# emonTx4-ESP32.net
KiCad netlist of a schematic drawn in EAGLE
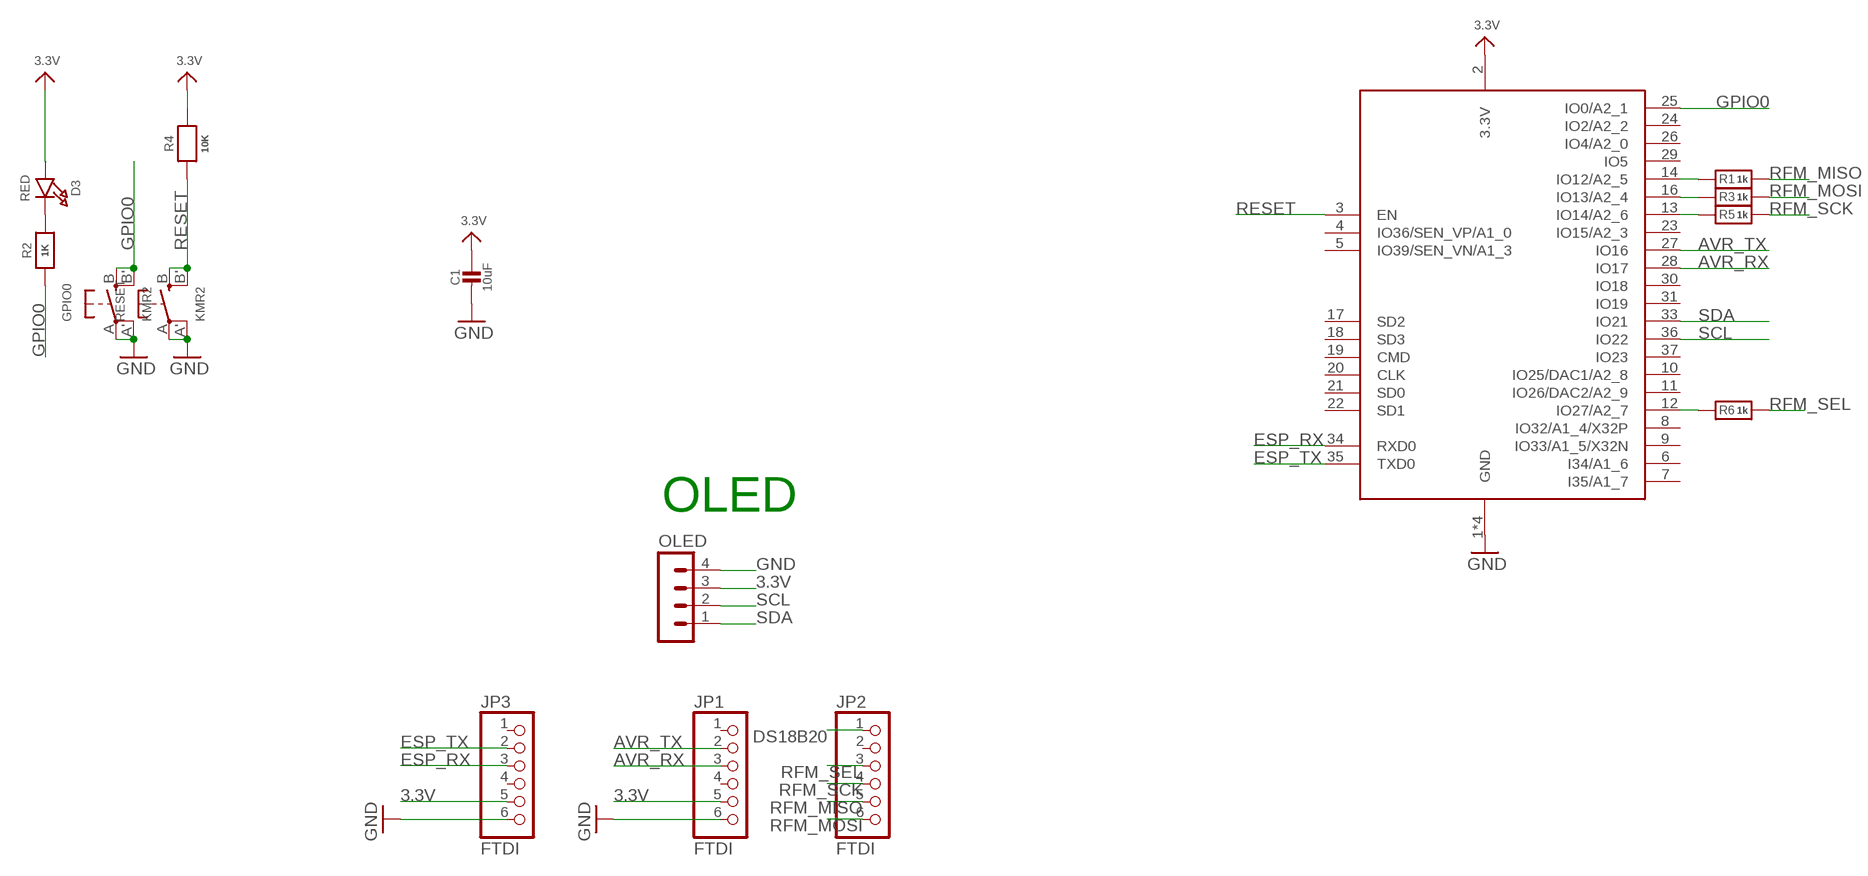
[diagram p0: schematic, sheet 1]

(export (version "E")
  (design (tool "Eeschema 10.0.6"))
  (components
    (comp (ref "C1")
      (value "10uF")
      (footprint "eagle-import:_0603")
      (libsource (lib "eagle-import") (part "CAP_CERAMIC_0603"))
    )
    (comp (ref "D3")
      (value "RED")
      (footprint "eagle-import:CHIPLED_0603")
      (libsource (lib "eagle-import") (part "LED0603"))
    )
    (comp (ref "GPIO0")
      (value "KMR2")
      (footprint "eagle-import:BTN_KMR2_4.6X2.8")
      (libsource (lib "eagle-import") (part "SWITCH_TACT_SMT4.6X2.8"))
    )
    (comp (ref "JP1")
      (value "FTDI")
      (footprint "eagle-import:1X06_ROUND_70")
      (libsource (lib "eagle-import") (part "HEADER-1X670MIL"))
    )
    (comp (ref "JP2")
      (value "FTDI")
      (footprint "eagle-import:1X06_ROUND_70")
      (libsource (lib "eagle-import") (part "HEADER-1X670MIL"))
    )
    (comp (ref "JP3")
      (value "FTDI")
      (footprint "eagle-import:1X06_ROUND_70")
      (libsource (lib "eagle-import") (part "HEADER-1X670MIL"))
    )
    (comp (ref "OLED")
      (value "MA04-1-OLEDOLED")
      (footprint "eagle-import:MA04-1-OLED")
      (libsource (lib "eagle-import") (part "MA04-1-OLEDOLED"))
    )
    (comp (ref "R1")
      (value "1k")
      (footprint "eagle-import:_0603")
      (libsource (lib "eagle-import") (part "RESISTOR_0603"))
    )
    (comp (ref "R2")
      (value "1K")
      (footprint "eagle-import:_0603")
      (libsource (lib "eagle-import") (part "RESISTOR_0603"))
    )
    (comp (ref "R3")
      (value "1k")
      (footprint "eagle-import:_0603")
      (libsource (lib "eagle-import") (part "RESISTOR_0603"))
    )
    (comp (ref "R4")
      (value "10K")
      (footprint "eagle-import:_0603")
      (libsource (lib "eagle-import") (part "RESISTOR_0603"))
    )
    (comp (ref "R5")
      (value "1k")
      (footprint "eagle-import:_0603")
      (libsource (lib "eagle-import") (part "RESISTOR_0603"))
    )
    (comp (ref "R6")
      (value "1k")
      (footprint "eagle-import:_0603")
      (libsource (lib "eagle-import") (part "RESISTOR_0603"))
    )
    (comp (ref "RESET")
      (value "KMR2")
      (footprint "eagle-import:BTN_KMR2_4.6X2.8")
      (libsource (lib "eagle-import") (part "SWITCH_TACT_SMT4.6X2.8"))
    )
    (comp (ref "X2")
      (value "ESP32_WROOM32")
      (footprint "eagle-import:WROOM32")
      (libsource (lib "eagle-import") (part "ESP32_WROOM32"))
    )
  )
  (nets
    (net (code "1") (name "/AVR_RX") (class "Default")
      (node (ref "JP1") (pin "3") (pinfunction "3_3") (pintype "passive"))
      (node (ref "X2") (pin "28") (pinfunction "IO17_28") (pintype "bidirectional"))
    )
    (net (code "2") (name "/AVR_TX") (class "Default")
      (node (ref "JP1") (pin "2") (pinfunction "2_2") (pintype "passive"))
      (node (ref "X2") (pin "27") (pinfunction "IO16_27") (pintype "bidirectional"))
    )
    (net (code "3") (name "/DS18B20") (class "Default")
      (node (ref "JP2") (pin "1") (pinfunction "1_1") (pintype "passive"))
    )
    (net (code "4") (name "/ESP_RX") (class "Default")
      (node (ref "JP3") (pin "3") (pinfunction "3_3") (pintype "passive"))
      (node (ref "X2") (pin "34") (pinfunction "RXD0_34") (pintype "input"))
    )
    (net (code "5") (name "/ESP_TX") (class "Default")
      (node (ref "JP3") (pin "2") (pinfunction "2_2") (pintype "passive"))
      (node (ref "X2") (pin "35") (pinfunction "TXD0_35") (pintype "output"))
    )
    (net (code "6") (name "/GPIO0") (class "Default")
      (node (ref "GPIO0") (pin "B") (pinfunction "S_B") (pintype "passive"))
      (node (ref "GPIO0") (pin "B'") (pinfunction "S1_B'") (pintype "passive"))
      (node (ref "R2") (pin "1") (pinfunction "1_1") (pintype "passive"))
      (node (ref "X2") (pin "25") (pinfunction "IO0/A2_1_25") (pintype "bidirectional"))
    )
    (net (code "7") (name "/RESET") (class "Default")
      (node (ref "R4") (pin "1") (pinfunction "1_1") (pintype "passive"))
      (node (ref "RESET") (pin "B") (pinfunction "S_B") (pintype "passive"))
      (node (ref "RESET") (pin "B'") (pinfunction "S1_B'") (pintype "passive"))
      (node (ref "X2") (pin "3") (pinfunction "EN_3") (pintype "input"))
    )
    (net (code "8") (name "/RFM_MISO") (class "Default")
      (node (ref "JP2") (pin "5") (pinfunction "5_5") (pintype "passive"))
      (node (ref "R1") (pin "1") (pinfunction "1_1") (pintype "passive"))
    )
    (net (code "9") (name "/RFM_MOSI") (class "Default")
      (node (ref "JP2") (pin "6") (pinfunction "6_6") (pintype "passive"))
      (node (ref "R3") (pin "1") (pinfunction "1_1") (pintype "passive"))
    )
    (net (code "10") (name "/RFM_SCK") (class "Default")
      (node (ref "JP2") (pin "4") (pinfunction "4_4") (pintype "passive"))
      (node (ref "R5") (pin "1") (pinfunction "1_1") (pintype "passive"))
    )
    (net (code "11") (name "/RFM_SEL") (class "Default")
      (node (ref "JP2") (pin "3") (pinfunction "3_3") (pintype "passive"))
      (node (ref "R6") (pin "1") (pinfunction "1_1") (pintype "passive"))
    )
    (net (code "12") (name "/SCL") (class "Default")
      (node (ref "OLED") (pin "2") (pinfunction "2_2") (pintype "passive"))
      (node (ref "X2") (pin "36") (pinfunction "IO22_36") (pintype "bidirectional"))
    )
    (net (code "13") (name "/SDA") (class "Default")
      (node (ref "OLED") (pin "1") (pinfunction "1_1") (pintype "passive"))
      (node (ref "X2") (pin "33") (pinfunction "IO21_33") (pintype "bidirectional"))
    )
    (net (code "14") (name "3.3V") (class "Default")
      (node (ref "C1") (pin "1") (pinfunction "1_1") (pintype "passive"))
      (node (ref "D3") (pin "A") (pinfunction "A_A") (pintype "passive"))
      (node (ref "JP1") (pin "5") (pinfunction "5_5") (pintype "passive"))
      (node (ref "JP3") (pin "5") (pinfunction "5_5") (pintype "passive"))
      (node (ref "OLED") (pin "3") (pinfunction "3_3") (pintype "passive"))
      (node (ref "R4") (pin "2") (pinfunction "2_2") (pintype "passive"))
      (node (ref "X2") (pin "2") (pinfunction "3.3V_2") (pintype "passive"))
    )
    (net (code "15") (name "GND") (class "Default")
      (node (ref "C1") (pin "2") (pinfunction "2_2") (pintype "passive"))
      (node (ref "GPIO0") (pin "A") (pinfunction "P_A") (pintype "passive"))
      (node (ref "GPIO0") (pin "A'") (pinfunction "P1_A'") (pintype "passive"))
      (node (ref "JP1") (pin "6") (pinfunction "6_6") (pintype "passive"))
      (node (ref "JP3") (pin "6") (pinfunction "6_6") (pintype "passive"))
      (node (ref "OLED") (pin "4") (pinfunction "4_4") (pintype "passive"))
      (node (ref "RESET") (pin "A") (pinfunction "P_A") (pintype "passive"))
      (node (ref "RESET") (pin "A'") (pinfunction "P1_A'") (pintype "passive"))
      (node (ref "X2") (pin "1") (pinfunction "GND_1") (pintype "passive"))
      (node (ref "X2") (pin "15") (pinfunction "GND_15") (pintype "passive"))
      (node (ref "X2") (pin "38") (pinfunction "GND_38") (pintype "passive"))
      (node (ref "X2") (pin "P$1") (pinfunction "GND_P$1") (pintype "passive"))
    )
    (net (code "16") (name "Net-(D3-PadC)") (class "Default")
      (node (ref "D3") (pin "C") (pinfunction "C_C") (pintype "passive"))
      (node (ref "R2") (pin "2") (pinfunction "2_2") (pintype "passive"))
    )
    (net (code "17") (name "Net-(X2-IO12{slash}A2_5)") (class "Default")
      (node (ref "R1") (pin "2") (pinfunction "2_2") (pintype "passive"))
      (node (ref "X2") (pin "14") (pinfunction "IO12/A2_5_14") (pintype "bidirectional"))
    )
    (net (code "18") (name "Net-(X2-IO13{slash}A2_4)") (class "Default")
      (node (ref "R3") (pin "2") (pinfunction "2_2") (pintype "passive"))
      (node (ref "X2") (pin "16") (pinfunction "IO13/A2_4_16") (pintype "bidirectional"))
    )
    (net (code "19") (name "Net-(X2-IO14{slash}A2_6)") (class "Default")
      (node (ref "R5") (pin "2") (pinfunction "2_2") (pintype "passive"))
      (node (ref "X2") (pin "13") (pinfunction "IO14/A2_6_13") (pintype "bidirectional"))
    )
    (net (code "20") (name "Net-(X2-IO27{slash}A2_7)") (class "Default")
      (node (ref "R6") (pin "2") (pinfunction "2_2") (pintype "passive"))
      (node (ref "X2") (pin "12") (pinfunction "IO27/A2_7_12") (pintype "bidirectional"))
    )
    (net (code "21") (name "unconnected-(JP1-Pad1)") (class "Default")
      (node (ref "JP1") (pin "1") (pinfunction "1_1") (pintype "passive"))
    )
    (net (code "22") (name "unconnected-(JP1-Pad4)") (class "Default")
      (node (ref "JP1") (pin "4") (pinfunction "4_4") (pintype "passive"))
    )
    (net (code "23") (name "unconnected-(JP2-Pad2)") (class "Default")
      (node (ref "JP2") (pin "2") (pinfunction "2_2") (pintype "passive"))
    )
    (net (code "24") (name "unconnected-(JP3-Pad1)") (class "Default")
      (node (ref "JP3") (pin "1") (pinfunction "1_1") (pintype "passive"))
    )
    (net (code "25") (name "unconnected-(JP3-Pad4)") (class "Default")
      (node (ref "JP3") (pin "4") (pinfunction "4_4") (pintype "passive"))
    )
    (net (code "26") (name "unconnected-(X2-CLK-Pad20)") (class "Default")
      (node (ref "X2") (pin "20") (pinfunction "CLK_20") (pintype "bidirectional"))
    )
    (net (code "27") (name "unconnected-(X2-CMD-Pad19)") (class "Default")
      (node (ref "X2") (pin "19") (pinfunction "CMD_19") (pintype "bidirectional"))
    )
    (net (code "28") (name "unconnected-(X2-I34{slash}A1_6-Pad6)") (class "Default")
      (node (ref "X2") (pin "6") (pinfunction "I34/A1_6_6") (pintype "bidirectional"))
    )
    (net (code "29") (name "unconnected-(X2-I35{slash}A1_7-Pad7)") (class "Default")
      (node (ref "X2") (pin "7") (pinfunction "I35/A1_7_7") (pintype "bidirectional"))
    )
    (net (code "30") (name "unconnected-(X2-IO2{slash}A2_2-Pad24)") (class "Default")
      (node (ref "X2") (pin "24") (pinfunction "IO2/A2_2_24") (pintype "bidirectional"))
    )
    (net (code "31") (name "unconnected-(X2-IO4{slash}A2_0-Pad26)") (class "Default")
      (node (ref "X2") (pin "26") (pinfunction "IO4/A2_0_26") (pintype "bidirectional"))
    )
    (net (code "32") (name "unconnected-(X2-IO5-Pad29)") (class "Default")
      (node (ref "X2") (pin "29") (pinfunction "IO5_29") (pintype "bidirectional"))
    )
    (net (code "33") (name "unconnected-(X2-IO15{slash}A2_3-Pad23)") (class "Default")
      (node (ref "X2") (pin "23") (pinfunction "IO15/A2_3_23") (pintype "bidirectional"))
    )
    (net (code "34") (name "unconnected-(X2-IO18-Pad30)") (class "Default")
      (node (ref "X2") (pin "30") (pinfunction "IO18_30") (pintype "bidirectional"))
    )
    (net (code "35") (name "unconnected-(X2-IO19-Pad31)") (class "Default")
      (node (ref "X2") (pin "31") (pinfunction "IO19_31") (pintype "bidirectional"))
    )
    (net (code "36") (name "unconnected-(X2-IO23-Pad37)") (class "Default")
      (node (ref "X2") (pin "37") (pinfunction "IO23_37") (pintype "bidirectional"))
    )
    (net (code "37") (name "unconnected-(X2-IO25{slash}DAC1{slash}A2_8-Pad10)") (class "Default")
      (node (ref "X2") (pin "10") (pinfunction "IO25/DAC1/A2_8_10") (pintype "bidirectional"))
    )
    (net (code "38") (name "unconnected-(X2-IO26{slash}DAC2{slash}A2_9-Pad11)") (class "Default")
      (node (ref "X2") (pin "11") (pinfunction "IO26/DAC2/A2_9_11") (pintype "bidirectional"))
    )
    (net (code "39") (name "unconnected-(X2-IO32{slash}A1_4{slash}X32P-Pad8)") (class "Default")
      (node (ref "X2") (pin "8") (pinfunction "IO32/A1_4/X32P_8") (pintype "bidirectional"))
    )
    (net (code "40") (name "unconnected-(X2-IO33{slash}A1_5{slash}X32N-Pad9)") (class "Default")
      (node (ref "X2") (pin "9") (pinfunction "IO33/A1_5/X32N_9") (pintype "bidirectional"))
    )
    (net (code "41") (name "unconnected-(X2-IO36{slash}SEN_VP{slash}A1_0-Pad4)") (class "Default")
      (node (ref "X2") (pin "4") (pinfunction "IO36/SEN_VP/A1_0_4") (pintype "passive"))
    )
    (net (code "42") (name "unconnected-(X2-IO39{slash}SEN_VN{slash}A1_3-Pad5)") (class "Default")
      (node (ref "X2") (pin "5") (pinfunction "IO39/SEN_VN/A1_3_5") (pintype "passive"))
    )
    (net (code "43") (name "unconnected-(X2-SD0-Pad21)") (class "Default")
      (node (ref "X2") (pin "21") (pinfunction "SD0_21") (pintype "bidirectional"))
    )
    (net (code "44") (name "unconnected-(X2-SD1-Pad22)") (class "Default")
      (node (ref "X2") (pin "22") (pinfunction "SD1_22") (pintype "bidirectional"))
    )
    (net (code "45") (name "unconnected-(X2-SD2-Pad17)") (class "Default")
      (node (ref "X2") (pin "17") (pinfunction "SD2_17") (pintype "bidirectional"))
    )
    (net (code "46") (name "unconnected-(X2-SD3-Pad18)") (class "Default")
      (node (ref "X2") (pin "18") (pinfunction "SD3_18") (pintype "bidirectional"))
    )
  )
)
